# M1501X.net
KiCad netlist of a schematic drawn in EAGLE
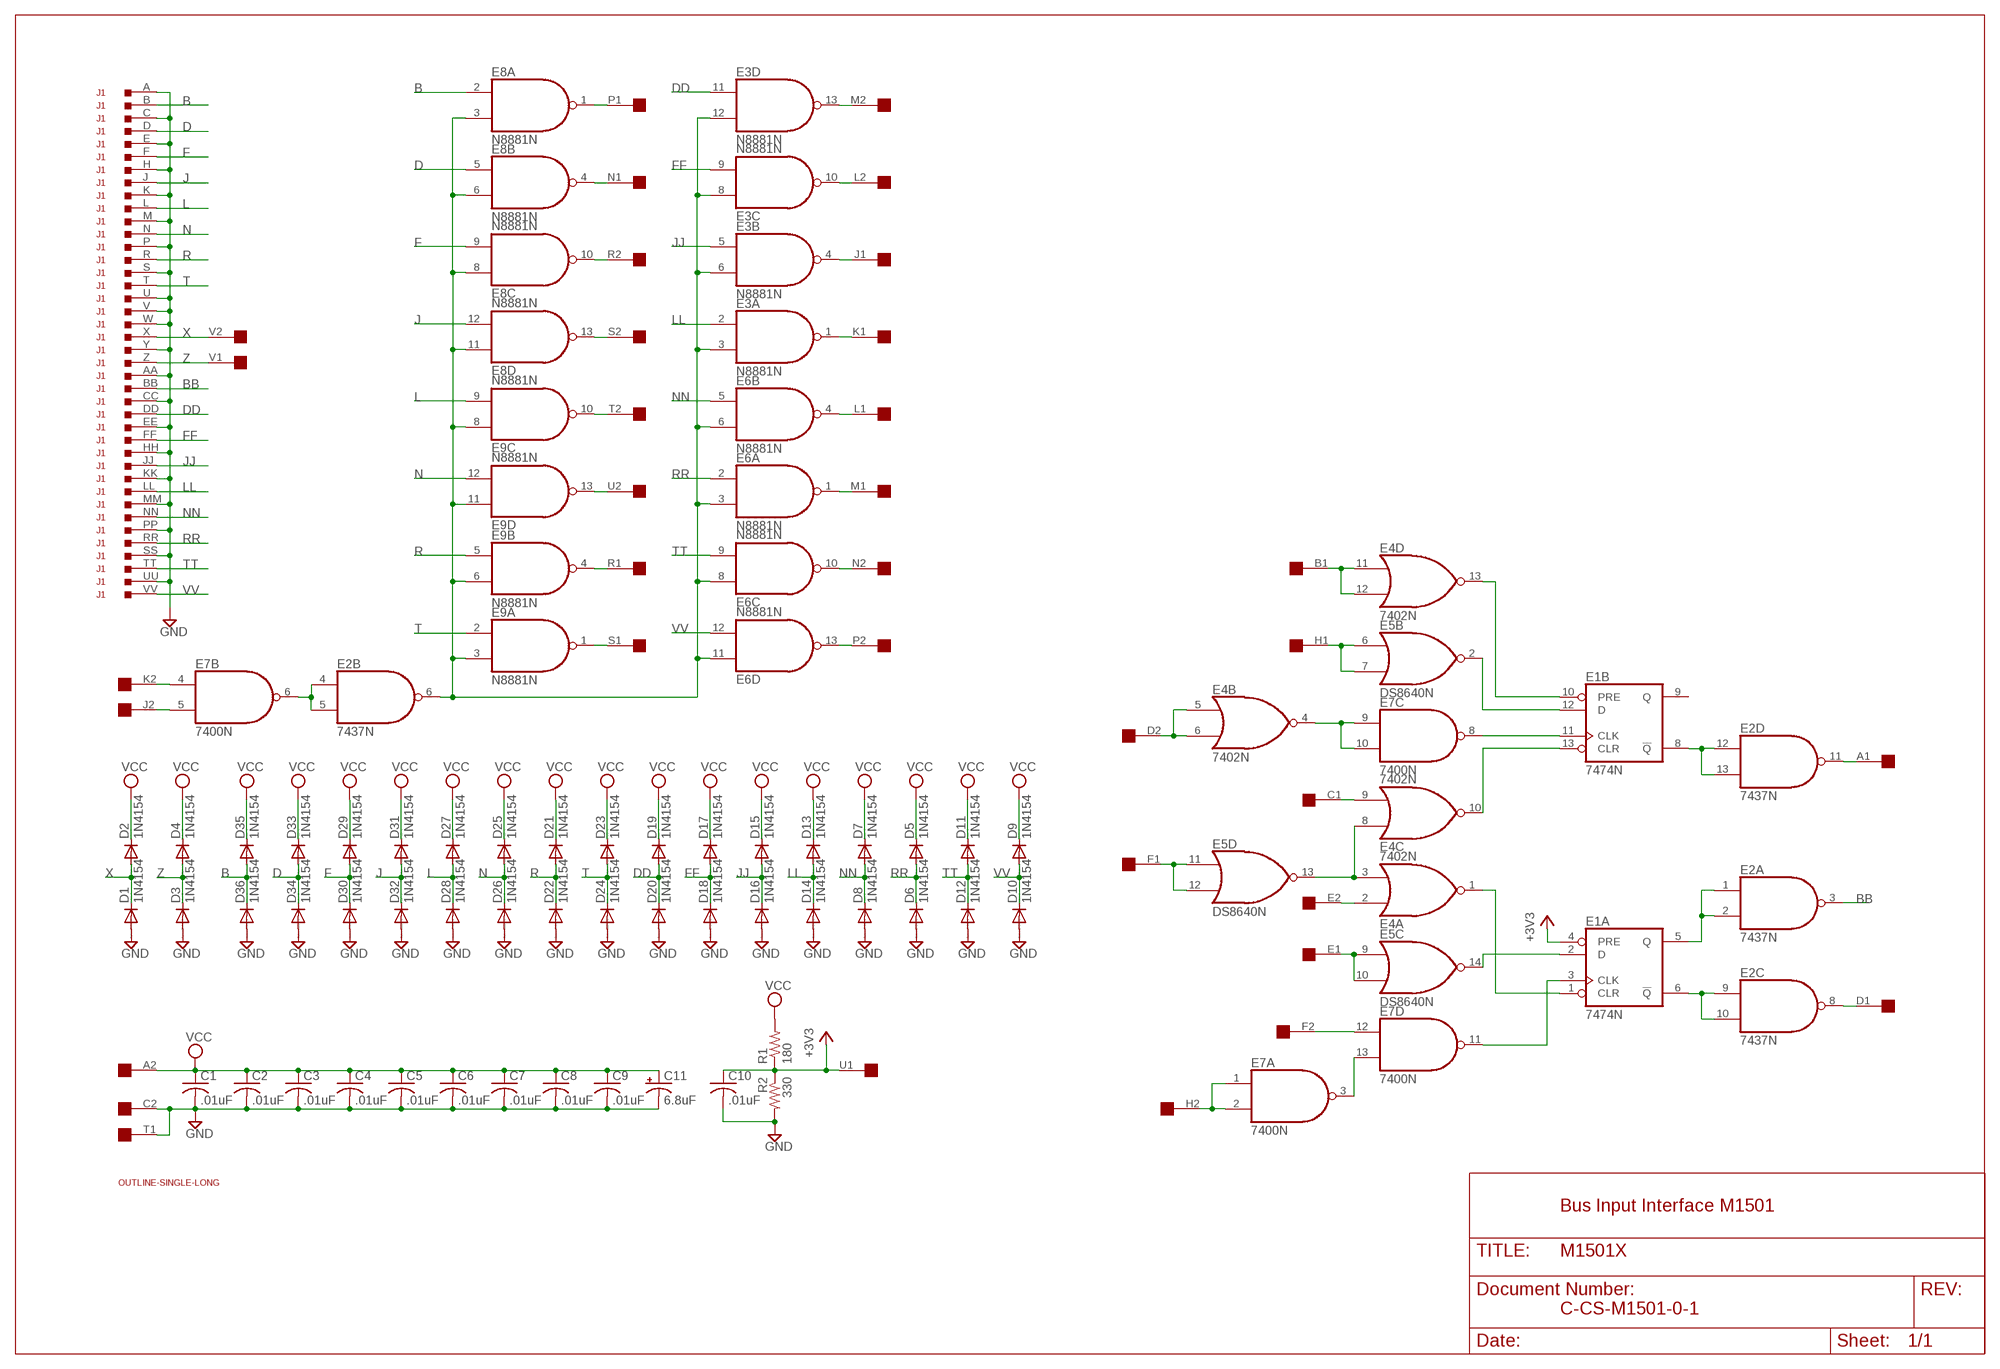
[diagram p0: schematic, sheet 1]

(export (version "E")
  (design (tool "Eeschema 10.0.6"))
  (components
    (comp (ref "C1")
      (value ".01uF")
      (footprint "eagle-import:C050-025X075")
      (libsource (lib "eagle-import") (part "C-US050-025X075"))
    )
    (comp (ref "C2")
      (value ".01uF")
      (footprint "eagle-import:C050-025X075")
      (libsource (lib "eagle-import") (part "C-US050-025X075"))
    )
    (comp (ref "C3")
      (value ".01uF")
      (footprint "eagle-import:C050-025X075")
      (libsource (lib "eagle-import") (part "C-US050-025X075"))
    )
    (comp (ref "C4")
      (value ".01uF")
      (footprint "eagle-import:C050-025X075")
      (libsource (lib "eagle-import") (part "C-US050-025X075"))
    )
    (comp (ref "C5")
      (value ".01uF")
      (footprint "eagle-import:C050-025X075")
      (libsource (lib "eagle-import") (part "C-US050-025X075"))
    )
    (comp (ref "C6")
      (value ".01uF")
      (footprint "eagle-import:C050-025X075")
      (libsource (lib "eagle-import") (part "C-US050-025X075"))
    )
    (comp (ref "C7")
      (value ".01uF")
      (footprint "eagle-import:C050-025X075")
      (libsource (lib "eagle-import") (part "C-US050-025X075"))
    )
    (comp (ref "C8")
      (value ".01uF")
      (footprint "eagle-import:C050-025X075")
      (libsource (lib "eagle-import") (part "C-US050-025X075"))
    )
    (comp (ref "C9")
      (value ".01uF")
      (footprint "eagle-import:C050-025X075")
      (libsource (lib "eagle-import") (part "C-US050-025X075"))
    )
    (comp (ref "C10")
      (value ".01uF")
      (footprint "eagle-import:C050-025X075")
      (libsource (lib "eagle-import") (part "C-US050-025X075"))
    )
    (comp (ref "C11")
      (value "6.8uF")
      (footprint "eagle-import:E12-8")
      (libsource (lib "eagle-import") (part "CPOL-USE20-8AXIAL"))
    )
    (comp (ref "D1")
      (value "1N4154")
      (footprint "eagle-import:DO35-10")
      (libsource (lib "eagle-import") (part "DIODE-DO35-10"))
    )
    (comp (ref "D2")
      (value "1N4154")
      (footprint "eagle-import:DO35-10")
      (libsource (lib "eagle-import") (part "DIODE-DO35-10"))
    )
    (comp (ref "D3")
      (value "1N4154")
      (footprint "eagle-import:DO35-10")
      (libsource (lib "eagle-import") (part "DIODE-DO35-10"))
    )
    (comp (ref "D4")
      (value "1N4154")
      (footprint "eagle-import:DO35-10")
      (libsource (lib "eagle-import") (part "DIODE-DO35-10"))
    )
    (comp (ref "D5")
      (value "1N4154")
      (footprint "eagle-import:DO35-10")
      (libsource (lib "eagle-import") (part "DIODE-DO35-10"))
    )
    (comp (ref "D6")
      (value "1N4154")
      (footprint "eagle-import:DO35-10")
      (libsource (lib "eagle-import") (part "DIODE-DO35-10"))
    )
    (comp (ref "D7")
      (value "1N4154")
      (footprint "eagle-import:DO35-10")
      (libsource (lib "eagle-import") (part "DIODE-DO35-10"))
    )
    (comp (ref "D8")
      (value "1N4154")
      (footprint "eagle-import:DO35-10")
      (libsource (lib "eagle-import") (part "DIODE-DO35-10"))
    )
    (comp (ref "D9")
      (value "1N4154")
      (footprint "eagle-import:DO35-10")
      (libsource (lib "eagle-import") (part "DIODE-DO35-10"))
    )
    (comp (ref "D10")
      (value "1N4154")
      (footprint "eagle-import:DO35-10")
      (libsource (lib "eagle-import") (part "DIODE-DO35-10"))
    )
    (comp (ref "D11")
      (value "1N4154")
      (footprint "eagle-import:DO35-10")
      (libsource (lib "eagle-import") (part "DIODE-DO35-10"))
    )
    (comp (ref "D12")
      (value "1N4154")
      (footprint "eagle-import:DO35-10")
      (libsource (lib "eagle-import") (part "DIODE-DO35-10"))
    )
    (comp (ref "D13")
      (value "1N4154")
      (footprint "eagle-import:DO35-10")
      (libsource (lib "eagle-import") (part "DIODE-DO35-10"))
    )
    (comp (ref "D14")
      (value "1N4154")
      (footprint "eagle-import:DO35-10")
      (libsource (lib "eagle-import") (part "DIODE-DO35-10"))
    )
    (comp (ref "D15")
      (value "1N4154")
      (footprint "eagle-import:DO35-10")
      (libsource (lib "eagle-import") (part "DIODE-DO35-10"))
    )
    (comp (ref "D16")
      (value "1N4154")
      (footprint "eagle-import:DO35-10")
      (libsource (lib "eagle-import") (part "DIODE-DO35-10"))
    )
    (comp (ref "D17")
      (value "1N4154")
      (footprint "eagle-import:DO35-10")
      (libsource (lib "eagle-import") (part "DIODE-DO35-10"))
    )
    (comp (ref "D18")
      (value "1N4154")
      (footprint "eagle-import:DO35-10")
      (libsource (lib "eagle-import") (part "DIODE-DO35-10"))
    )
    (comp (ref "D19")
      (value "1N4154")
      (footprint "eagle-import:DO35-10")
      (libsource (lib "eagle-import") (part "DIODE-DO35-10"))
    )
    (comp (ref "D20")
      (value "1N4154")
      (footprint "eagle-import:DO35-10")
      (libsource (lib "eagle-import") (part "DIODE-DO35-10"))
    )
    (comp (ref "D21")
      (value "1N4154")
      (footprint "eagle-import:DO35-10")
      (libsource (lib "eagle-import") (part "DIODE-DO35-10"))
    )
    (comp (ref "D22")
      (value "1N4154")
      (footprint "eagle-import:DO35-10")
      (libsource (lib "eagle-import") (part "DIODE-DO35-10"))
    )
    (comp (ref "D23")
      (value "1N4154")
      (footprint "eagle-import:DO35-10")
      (libsource (lib "eagle-import") (part "DIODE-DO35-10"))
    )
    (comp (ref "D24")
      (value "1N4154")
      (footprint "eagle-import:DO35-10")
      (libsource (lib "eagle-import") (part "DIODE-DO35-10"))
    )
    (comp (ref "D25")
      (value "1N4154")
      (footprint "eagle-import:DO35-10")
      (libsource (lib "eagle-import") (part "DIODE-DO35-10"))
    )
    (comp (ref "D26")
      (value "1N4154")
      (footprint "eagle-import:DO35-10")
      (libsource (lib "eagle-import") (part "DIODE-DO35-10"))
    )
    (comp (ref "D27")
      (value "1N4154")
      (footprint "eagle-import:DO35-10")
      (libsource (lib "eagle-import") (part "DIODE-DO35-10"))
    )
    (comp (ref "D28")
      (value "1N4154")
      (footprint "eagle-import:DO35-10")
      (libsource (lib "eagle-import") (part "DIODE-DO35-10"))
    )
    (comp (ref "D29")
      (value "1N4154")
      (footprint "eagle-import:DO35-10")
      (libsource (lib "eagle-import") (part "DIODE-DO35-10"))
    )
    (comp (ref "D30")
      (value "1N4154")
      (footprint "eagle-import:DO35-10")
      (libsource (lib "eagle-import") (part "DIODE-DO35-10"))
    )
    (comp (ref "D31")
      (value "1N4154")
      (footprint "eagle-import:DO35-10")
      (libsource (lib "eagle-import") (part "DIODE-DO35-10"))
    )
    (comp (ref "D32")
      (value "1N4154")
      (footprint "eagle-import:DO35-10")
      (libsource (lib "eagle-import") (part "DIODE-DO35-10"))
    )
    (comp (ref "D33")
      (value "1N4154")
      (footprint "eagle-import:DO35-10")
      (libsource (lib "eagle-import") (part "DIODE-DO35-10"))
    )
    (comp (ref "D34")
      (value "1N4154")
      (footprint "eagle-import:DO35-10")
      (libsource (lib "eagle-import") (part "DIODE-DO35-10"))
    )
    (comp (ref "D35")
      (value "1N4154")
      (footprint "eagle-import:DO35-10")
      (libsource (lib "eagle-import") (part "DIODE-DO35-10"))
    )
    (comp (ref "D36")
      (value "1N4154")
      (footprint "eagle-import:DO35-10")
      (libsource (lib "eagle-import") (part "DIODE-DO35-10"))
    )
    (comp (ref "E1")
      (value "7474N")
      (footprint "eagle-import:DIL14")
      (libsource (lib "eagle-import") (part "7474NS"))
    )
    (comp (ref "E2")
      (value "7437N")
      (footprint "eagle-import:DIL14")
      (libsource (lib "eagle-import") (part "7437N"))
    )
    (comp (ref "E3")
      (value "N8881N")
      (footprint "eagle-import:DIL14")
      (libsource (lib "eagle-import") (part "N8881N"))
    )
    (comp (ref "E4")
      (value "7402N")
      (footprint "eagle-import:DIL14")
      (libsource (lib "eagle-import") (part "7402N"))
    )
    (comp (ref "E5")
      (value "DS8640N")
      (footprint "eagle-import:DIL14")
      (libsource (lib "eagle-import") (part "DS8640N"))
    )
    (comp (ref "E6")
      (value "N8881N")
      (footprint "eagle-import:DIL14")
      (libsource (lib "eagle-import") (part "N8881N"))
    )
    (comp (ref "E7")
      (value "7400N")
      (footprint "eagle-import:DIL14")
      (libsource (lib "eagle-import") (part "7400N"))
    )
    (comp (ref "E8")
      (value "N8881N")
      (footprint "eagle-import:DIL14")
      (libsource (lib "eagle-import") (part "N8881N"))
    )
    (comp (ref "E9")
      (value "N8881N")
      (footprint "eagle-import:DIL14")
      (libsource (lib "eagle-import") (part "N8881N"))
    )
    (comp (ref "J1")
      (value "DEC40PINSH")
      (footprint "eagle-import:DEC40PINH")
      (libsource (lib "eagle-import") (part "DEC40PINSH"))
    )
    (comp (ref "R1")
      (value "180")
      (footprint "eagle-import:0207_10")
      (libsource (lib "eagle-import") (part "R-US_0207/10"))
    )
    (comp (ref "R2")
      (value "330")
      (footprint "eagle-import:0207_10")
      (libsource (lib "eagle-import") (part "R-US_0207/10"))
    )
    (comp (ref "U$1")
      (value "OUTLINE-SINGLE-LONG")
      (footprint "eagle-import:SINGLE-LONG")
      (libsource (lib "eagle-import") (part "OUTLINE-SINGLE-LONG"))
    )
    (comp (ref "U$2")
      (value "SINGLE")
      (footprint "eagle-import:EDGE-CON2")
      (libsource (lib "eagle-import") (part "SINGLE"))
    )
  )
  (nets
    (net (code "1") (name "+3V3") (class "Default")
      (node (ref "C10") (pin "1") (pinfunction "1_1") (pintype "passive"))
      (node (ref "E1") (pin "4") (pinfunction "PRE_4") (pintype "input"))
      (node (ref "R1") (pin "1") (pinfunction "1_1") (pintype "passive"))
      (node (ref "R2") (pin "1") (pinfunction "1_1") (pintype "passive"))
      (node (ref "U$2") (pin "U1") (pinfunction "1_U1") (pintype "bidirectional"))
    )
    (net (code "2") (name "/B") (class "Default")
      (node (ref "D35") (pin "A") (pinfunction "A_A") (pintype "passive"))
      (node (ref "D36") (pin "C") (pinfunction "C_C") (pintype "passive"))
      (node (ref "E8") (pin "2") (pinfunction "I0_2") (pintype "input"))
      (node (ref "J1") (pin "B") (pinfunction "P$2_B") (pintype "passive"))
    )
    (net (code "3") (name "/BB") (class "Default")
      (node (ref "E2") (pin "3") (pinfunction "O_3") (pintype "output"))
      (node (ref "J1") (pin "BB") (pinfunction "P$2_BB") (pintype "passive"))
    )
    (net (code "4") (name "/D") (class "Default")
      (node (ref "D33") (pin "A") (pinfunction "A_A") (pintype "passive"))
      (node (ref "D34") (pin "C") (pinfunction "C_C") (pintype "passive"))
      (node (ref "E8") (pin "5") (pinfunction "I0_5") (pintype "input"))
      (node (ref "J1") (pin "D") (pinfunction "P$2_D") (pintype "passive"))
    )
    (net (code "5") (name "/DD") (class "Default")
      (node (ref "D19") (pin "A") (pinfunction "A_A") (pintype "passive"))
      (node (ref "D20") (pin "C") (pinfunction "C_C") (pintype "passive"))
      (node (ref "E3") (pin "11") (pinfunction "I0_11") (pintype "input"))
      (node (ref "J1") (pin "DD") (pinfunction "P$2_DD") (pintype "passive"))
    )
    (net (code "6") (name "/F") (class "Default")
      (node (ref "D29") (pin "A") (pinfunction "A_A") (pintype "passive"))
      (node (ref "D30") (pin "C") (pinfunction "C_C") (pintype "passive"))
      (node (ref "E8") (pin "9") (pinfunction "I1_9") (pintype "input"))
      (node (ref "J1") (pin "F") (pinfunction "P$2_F") (pintype "passive"))
    )
    (net (code "7") (name "/FF") (class "Default")
      (node (ref "D17") (pin "A") (pinfunction "A_A") (pintype "passive"))
      (node (ref "D18") (pin "C") (pinfunction "C_C") (pintype "passive"))
      (node (ref "E3") (pin "9") (pinfunction "I1_9") (pintype "input"))
      (node (ref "J1") (pin "FF") (pinfunction "P$2_FF") (pintype "passive"))
    )
    (net (code "8") (name "/J") (class "Default")
      (node (ref "D31") (pin "A") (pinfunction "A_A") (pintype "passive"))
      (node (ref "D32") (pin "C") (pinfunction "C_C") (pintype "passive"))
      (node (ref "E8") (pin "12") (pinfunction "I1_12") (pintype "input"))
      (node (ref "J1") (pin "J") (pinfunction "P$2_J") (pintype "passive"))
    )
    (net (code "9") (name "/JJ") (class "Default")
      (node (ref "D15") (pin "A") (pinfunction "A_A") (pintype "passive"))
      (node (ref "D16") (pin "C") (pinfunction "C_C") (pintype "passive"))
      (node (ref "E3") (pin "5") (pinfunction "I0_5") (pintype "input"))
      (node (ref "J1") (pin "JJ") (pinfunction "P$2_JJ") (pintype "passive"))
    )
    (net (code "10") (name "/L") (class "Default")
      (node (ref "D27") (pin "A") (pinfunction "A_A") (pintype "passive"))
      (node (ref "D28") (pin "C") (pinfunction "C_C") (pintype "passive"))
      (node (ref "E9") (pin "9") (pinfunction "I1_9") (pintype "input"))
      (node (ref "J1") (pin "L") (pinfunction "P$2_L") (pintype "passive"))
    )
    (net (code "11") (name "/LL") (class "Default")
      (node (ref "D13") (pin "A") (pinfunction "A_A") (pintype "passive"))
      (node (ref "D14") (pin "C") (pinfunction "C_C") (pintype "passive"))
      (node (ref "E3") (pin "2") (pinfunction "I0_2") (pintype "input"))
      (node (ref "J1") (pin "LL") (pinfunction "P$2_LL") (pintype "passive"))
    )
    (net (code "12") (name "/N") (class "Default")
      (node (ref "D25") (pin "A") (pinfunction "A_A") (pintype "passive"))
      (node (ref "D26") (pin "C") (pinfunction "C_C") (pintype "passive"))
      (node (ref "E9") (pin "12") (pinfunction "I1_12") (pintype "input"))
      (node (ref "J1") (pin "N") (pinfunction "P$2_N") (pintype "passive"))
    )
    (net (code "13") (name "/NN") (class "Default")
      (node (ref "D7") (pin "A") (pinfunction "A_A") (pintype "passive"))
      (node (ref "D8") (pin "C") (pinfunction "C_C") (pintype "passive"))
      (node (ref "E6") (pin "5") (pinfunction "I0_5") (pintype "input"))
      (node (ref "J1") (pin "NN") (pinfunction "P$2_NN") (pintype "passive"))
    )
    (net (code "14") (name "/R") (class "Default")
      (node (ref "D21") (pin "A") (pinfunction "A_A") (pintype "passive"))
      (node (ref "D22") (pin "C") (pinfunction "C_C") (pintype "passive"))
      (node (ref "E9") (pin "5") (pinfunction "I0_5") (pintype "input"))
      (node (ref "J1") (pin "R") (pinfunction "P$2_R") (pintype "passive"))
    )
    (net (code "15") (name "/RR") (class "Default")
      (node (ref "D5") (pin "A") (pinfunction "A_A") (pintype "passive"))
      (node (ref "D6") (pin "C") (pinfunction "C_C") (pintype "passive"))
      (node (ref "E6") (pin "2") (pinfunction "I0_2") (pintype "input"))
      (node (ref "J1") (pin "RR") (pinfunction "P$2_RR") (pintype "passive"))
    )
    (net (code "16") (name "/T") (class "Default")
      (node (ref "D23") (pin "A") (pinfunction "A_A") (pintype "passive"))
      (node (ref "D24") (pin "C") (pinfunction "C_C") (pintype "passive"))
      (node (ref "E9") (pin "2") (pinfunction "I0_2") (pintype "input"))
      (node (ref "J1") (pin "T") (pinfunction "P$2_T") (pintype "passive"))
    )
    (net (code "17") (name "/TT") (class "Default")
      (node (ref "D11") (pin "A") (pinfunction "A_A") (pintype "passive"))
      (node (ref "D12") (pin "C") (pinfunction "C_C") (pintype "passive"))
      (node (ref "E6") (pin "9") (pinfunction "I1_9") (pintype "input"))
      (node (ref "J1") (pin "TT") (pinfunction "P$2_TT") (pintype "passive"))
    )
    (net (code "18") (name "/VV") (class "Default")
      (node (ref "D10") (pin "C") (pinfunction "C_C") (pintype "passive"))
      (node (ref "D9") (pin "A") (pinfunction "A_A") (pintype "passive"))
      (node (ref "E6") (pin "12") (pinfunction "I1_12") (pintype "input"))
      (node (ref "J1") (pin "VV") (pinfunction "P$2_VV") (pintype "passive"))
    )
    (net (code "19") (name "/X") (class "Default")
      (node (ref "D1") (pin "C") (pinfunction "C_C") (pintype "passive"))
      (node (ref "D2") (pin "A") (pinfunction "A_A") (pintype "passive"))
      (node (ref "J1") (pin "X") (pinfunction "P$2_X") (pintype "passive"))
      (node (ref "U$2") (pin "V2") (pinfunction "1_V2") (pintype "bidirectional"))
    )
    (net (code "20") (name "/Z") (class "Default")
      (node (ref "D3") (pin "C") (pinfunction "C_C") (pintype "passive"))
      (node (ref "D4") (pin "A") (pinfunction "A_A") (pintype "passive"))
      (node (ref "J1") (pin "Z") (pinfunction "P$2_Z") (pintype "passive"))
      (node (ref "U$2") (pin "V1") (pinfunction "1_V1") (pintype "bidirectional"))
    )
    (net (code "21") (name "GND") (class "Default")
      (node (ref "C1") (pin "2") (pinfunction "2_2") (pintype "passive"))
      (node (ref "C10") (pin "2") (pinfunction "2_2") (pintype "passive"))
      (node (ref "C11") (pin "-") (pinfunction "-_-") (pintype "passive"))
      (node (ref "C2") (pin "2") (pinfunction "2_2") (pintype "passive"))
      (node (ref "C3") (pin "2") (pinfunction "2_2") (pintype "passive"))
      (node (ref "C4") (pin "2") (pinfunction "2_2") (pintype "passive"))
      (node (ref "C5") (pin "2") (pinfunction "2_2") (pintype "passive"))
      (node (ref "C6") (pin "2") (pinfunction "2_2") (pintype "passive"))
      (node (ref "C7") (pin "2") (pinfunction "2_2") (pintype "passive"))
      (node (ref "C8") (pin "2") (pinfunction "2_2") (pintype "passive"))
      (node (ref "C9") (pin "2") (pinfunction "2_2") (pintype "passive"))
      (node (ref "D1") (pin "A") (pinfunction "A_A") (pintype "passive"))
      (node (ref "D10") (pin "A") (pinfunction "A_A") (pintype "passive"))
      (node (ref "D12") (pin "A") (pinfunction "A_A") (pintype "passive"))
      (node (ref "D14") (pin "A") (pinfunction "A_A") (pintype "passive"))
      (node (ref "D16") (pin "A") (pinfunction "A_A") (pintype "passive"))
      (node (ref "D18") (pin "A") (pinfunction "A_A") (pintype "passive"))
      (node (ref "D20") (pin "A") (pinfunction "A_A") (pintype "passive"))
      (node (ref "D22") (pin "A") (pinfunction "A_A") (pintype "passive"))
      (node (ref "D24") (pin "A") (pinfunction "A_A") (pintype "passive"))
      (node (ref "D26") (pin "A") (pinfunction "A_A") (pintype "passive"))
      (node (ref "D28") (pin "A") (pinfunction "A_A") (pintype "passive"))
      (node (ref "D3") (pin "A") (pinfunction "A_A") (pintype "passive"))
      (node (ref "D30") (pin "A") (pinfunction "A_A") (pintype "passive"))
      (node (ref "D32") (pin "A") (pinfunction "A_A") (pintype "passive"))
      (node (ref "D34") (pin "A") (pinfunction "A_A") (pintype "passive"))
      (node (ref "D36") (pin "A") (pinfunction "A_A") (pintype "passive"))
      (node (ref "D6") (pin "A") (pinfunction "A_A") (pintype "passive"))
      (node (ref "D8") (pin "A") (pinfunction "A_A") (pintype "passive"))
      (node (ref "J1") (pin "A") (pinfunction "P$2_A") (pintype "passive"))
      (node (ref "J1") (pin "AA") (pinfunction "P$2_AA") (pintype "passive"))
      (node (ref "J1") (pin "C") (pinfunction "P$2_C") (pintype "passive"))
      (node (ref "J1") (pin "CC") (pinfunction "P$2_CC") (pintype "passive"))
      (node (ref "J1") (pin "E") (pinfunction "P$2_E") (pintype "passive"))
      (node (ref "J1") (pin "EE") (pinfunction "P$2_EE") (pintype "passive"))
      (node (ref "J1") (pin "H") (pinfunction "P$2_H") (pintype "passive"))
      (node (ref "J1") (pin "HH") (pinfunction "P$2_HH") (pintype "passive"))
      (node (ref "J1") (pin "K") (pinfunction "P$2_K") (pintype "passive"))
      (node (ref "J1") (pin "KK") (pinfunction "P$2_KK") (pintype "passive"))
      (node (ref "J1") (pin "M") (pinfunction "P$2_M") (pintype "passive"))
      (node (ref "J1") (pin "MM") (pinfunction "P$2_MM") (pintype "passive"))
      (node (ref "J1") (pin "P") (pinfunction "P$2_P") (pintype "passive"))
      (node (ref "J1") (pin "PP") (pinfunction "P$2_PP") (pintype "passive"))
      (node (ref "J1") (pin "S") (pinfunction "P$2_S") (pintype "passive"))
      (node (ref "J1") (pin "SS") (pinfunction "P$2_SS") (pintype "passive"))
      (node (ref "J1") (pin "U") (pinfunction "P$2_U") (pintype "passive"))
      (node (ref "J1") (pin "UU") (pinfunction "P$2_UU") (pintype "passive"))
      (node (ref "J1") (pin "V") (pinfunction "P$2_V") (pintype "passive"))
      (node (ref "J1") (pin "W") (pinfunction "P$2_W") (pintype "passive"))
      (node (ref "J1") (pin "Y") (pinfunction "P$2_Y") (pintype "passive"))
      (node (ref "R2") (pin "2") (pinfunction "2_2") (pintype "passive"))
      (node (ref "U$2") (pin "C2") (pinfunction "1_C2") (pintype "bidirectional"))
      (node (ref "U$2") (pin "T1") (pinfunction "1_T1") (pintype "bidirectional"))
    )
    (net (code "22") (name "Net-(E1A-CLK)") (class "Default")
      (node (ref "E1") (pin "3") (pinfunction "CLK_3") (pintype "input"))
      (node (ref "E7") (pin "11") (pinfunction "O_11") (pintype "output"))
    )
    (net (code "23") (name "Net-(E1A-CLR)") (class "Default")
      (node (ref "E1") (pin "1") (pinfunction "CLR_1") (pintype "input"))
      (node (ref "E4") (pin "1") (pinfunction "O_1") (pintype "output"))
    )
    (net (code "24") (name "Net-(E1A-D)") (class "Default")
      (node (ref "E1") (pin "2") (pinfunction "D_2") (pintype "input"))
      (node (ref "E5") (pin "14") (pinfunction "O_14") (pintype "output"))
    )
    (net (code "25") (name "Net-(E1A-Q)") (class "Default")
      (node (ref "E1") (pin "5") (pinfunction "Q_5") (pintype "output"))
      (node (ref "E2") (pin "1") (pinfunction "I0_1") (pintype "input"))
      (node (ref "E2") (pin "2") (pinfunction "I1_2") (pintype "input"))
    )
    (net (code "26") (name "Net-(E1A-~{Q})") (class "Default")
      (node (ref "E1") (pin "6") (pinfunction "~{Q}_6") (pintype "output"))
      (node (ref "E2") (pin "10") (pinfunction "I1_10") (pintype "input"))
      (node (ref "E2") (pin "9") (pinfunction "I0_9") (pintype "input"))
    )
    (net (code "27") (name "Net-(E1B-CLK)") (class "Default")
      (node (ref "E1") (pin "11") (pinfunction "CLK_11") (pintype "input"))
      (node (ref "E7") (pin "8") (pinfunction "O_8") (pintype "output"))
    )
    (net (code "28") (name "Net-(E1B-CLR)") (class "Default")
      (node (ref "E1") (pin "13") (pinfunction "CLR_13") (pintype "input"))
      (node (ref "E4") (pin "10") (pinfunction "O_10") (pintype "output"))
    )
    (net (code "29") (name "Net-(E1B-D)") (class "Default")
      (node (ref "E1") (pin "12") (pinfunction "D_12") (pintype "input"))
      (node (ref "E5") (pin "2") (pinfunction "O_2") (pintype "output"))
    )
    (net (code "30") (name "Net-(E1B-PRE)") (class "Default")
      (node (ref "E1") (pin "10") (pinfunction "PRE_10") (pintype "input"))
      (node (ref "E4") (pin "13") (pinfunction "O_13") (pintype "output"))
    )
    (net (code "31") (name "Net-(E1B-~{Q})") (class "Default")
      (node (ref "E1") (pin "8") (pinfunction "~{Q}_8") (pintype "output"))
      (node (ref "E2") (pin "12") (pinfunction "I0_12") (pintype "input"))
      (node (ref "E2") (pin "13") (pinfunction "I1_13") (pintype "input"))
    )
    (net (code "32") (name "Net-(E2B-I0)") (class "Default")
      (node (ref "E2") (pin "4") (pinfunction "I0_4") (pintype "input"))
      (node (ref "E2") (pin "5") (pinfunction "I1_5") (pintype "input"))
      (node (ref "E7") (pin "6") (pinfunction "O_6") (pintype "output"))
    )
    (net (code "33") (name "Net-(E2B-O)") (class "Default")
      (node (ref "E2") (pin "6") (pinfunction "O_6") (pintype "output"))
      (node (ref "E3") (pin "12") (pinfunction "I1_12") (pintype "input"))
      (node (ref "E3") (pin "3") (pinfunction "I1_3") (pintype "input"))
      (node (ref "E3") (pin "6") (pinfunction "I1_6") (pintype "input"))
      (node (ref "E3") (pin "8") (pinfunction "I0_8") (pintype "input"))
      (node (ref "E6") (pin "11") (pinfunction "I0_11") (pintype "input"))
      (node (ref "E6") (pin "3") (pinfunction "I1_3") (pintype "input"))
      (node (ref "E6") (pin "6") (pinfunction "I1_6") (pintype "input"))
      (node (ref "E6") (pin "8") (pinfunction "I0_8") (pintype "input"))
      (node (ref "E8") (pin "11") (pinfunction "I0_11") (pintype "input"))
      (node (ref "E8") (pin "3") (pinfunction "I1_3") (pintype "input"))
      (node (ref "E8") (pin "6") (pinfunction "I1_6") (pintype "input"))
      (node (ref "E8") (pin "8") (pinfunction "I0_8") (pintype "input"))
      (node (ref "E9") (pin "11") (pinfunction "I0_11") (pintype "input"))
      (node (ref "E9") (pin "3") (pinfunction "I1_3") (pintype "input"))
      (node (ref "E9") (pin "6") (pinfunction "I1_6") (pintype "input"))
      (node (ref "E9") (pin "8") (pinfunction "I0_8") (pintype "input"))
    )
    (net (code "34") (name "Net-(E2C-O)") (class "Default")
      (node (ref "E2") (pin "8") (pinfunction "O_8") (pintype "output"))
      (node (ref "U$2") (pin "D1") (pinfunction "1_D1") (pintype "bidirectional"))
    )
    (net (code "35") (name "Net-(E2D-O)") (class "Default")
      (node (ref "E2") (pin "11") (pinfunction "O_11") (pintype "output"))
      (node (ref "U$2") (pin "A1") (pinfunction "1_A1") (pintype "bidirectional"))
    )
    (net (code "36") (name "Net-(E3A-O)") (class "Default")
      (node (ref "E3") (pin "1") (pinfunction "O_1") (pintype "open_collector"))
      (node (ref "U$2") (pin "K1") (pinfunction "1_K1") (pintype "bidirectional"))
    )
    (net (code "37") (name "Net-(E3B-O)") (class "Default")
      (node (ref "E3") (pin "4") (pinfunction "O_4") (pintype "open_collector"))
      (node (ref "U$2") (pin "J1") (pinfunction "1_J1") (pintype "bidirectional"))
    )
    (net (code "38") (name "Net-(E3C-O)") (class "Default")
      (node (ref "E3") (pin "10") (pinfunction "O_10") (pintype "open_collector"))
      (node (ref "U$2") (pin "L2") (pinfunction "1_L2") (pintype "bidirectional"))
    )
    (net (code "39") (name "Net-(E3D-O)") (class "Default")
      (node (ref "E3") (pin "13") (pinfunction "O_13") (pintype "open_collector"))
      (node (ref "U$2") (pin "M2") (pinfunction "1_M2") (pintype "bidirectional"))
    )
    (net (code "40") (name "Net-(E4A-I0)") (class "Default")
      (node (ref "E4") (pin "2") (pinfunction "I0_2") (pintype "input"))
      (node (ref "U$2") (pin "E2") (pinfunction "1_E2") (pintype "bidirectional"))
    )
    (net (code "41") (name "Net-(E4A-I1)") (class "Default")
      (node (ref "E4") (pin "3") (pinfunction "I1_3") (pintype "input"))
      (node (ref "E4") (pin "8") (pinfunction "I0_8") (pintype "input"))
      (node (ref "E5") (pin "13") (pinfunction "O_13") (pintype "output"))
    )
    (net (code "42") (name "Net-(E4B-I0)") (class "Default")
      (node (ref "E4") (pin "5") (pinfunction "I0_5") (pintype "input"))
      (node (ref "E4") (pin "6") (pinfunction "I1_6") (pintype "input"))
      (node (ref "U$2") (pin "D2") (pinfunction "1_D2") (pintype "bidirectional"))
    )
    (net (code "43") (name "Net-(E4B-O)") (class "Default")
      (node (ref "E4") (pin "4") (pinfunction "O_4") (pintype "output"))
      (node (ref "E7") (pin "10") (pinfunction "I1_10") (pintype "input"))
      (node (ref "E7") (pin "9") (pinfunction "I0_9") (pintype "input"))
    )
    (net (code "44") (name "Net-(E4C-I1)") (class "Default")
      (node (ref "E4") (pin "9") (pinfunction "I1_9") (pintype "input"))
      (node (ref "U$2") (pin "C1") (pinfunction "1_C1") (pintype "bidirectional"))
    )
    (net (code "45") (name "Net-(E4D-I0)") (class "Default")
      (node (ref "E4") (pin "11") (pinfunction "I0_11") (pintype "input"))
      (node (ref "E4") (pin "12") (pinfunction "I1_12") (pintype "input"))
      (node (ref "U$2") (pin "B1") (pinfunction "1_B1") (pintype "bidirectional"))
    )
    (net (code "46") (name "Net-(E5B-I0)") (class "Default")
      (node (ref "E5") (pin "6") (pinfunction "I0_6") (pintype "input"))
      (node (ref "E5") (pin "7") (pinfunction "I1_7") (pintype "input"))
      (node (ref "U$2") (pin "H1") (pinfunction "1_H1") (pintype "bidirectional"))
    )
    (net (code "47") (name "Net-(E5C-I0)") (class "Default")
      (node (ref "E5") (pin "10") (pinfunction "I1_10") (pintype "input"))
      (node (ref "E5") (pin "9") (pinfunction "I0_9") (pintype "input"))
      (node (ref "U$2") (pin "E1") (pinfunction "1_E1") (pintype "bidirectional"))
    )
    (net (code "48") (name "Net-(E5D-I0)") (class "Default")
      (node (ref "E5") (pin "11") (pinfunction "I0_11") (pintype "input"))
      (node (ref "E5") (pin "12") (pinfunction "I1_12") (pintype "input"))
      (node (ref "U$2") (pin "F1") (pinfunction "1_F1") (pintype "bidirectional"))
    )
    (net (code "49") (name "Net-(E6A-O)") (class "Default")
      (node (ref "E6") (pin "1") (pinfunction "O_1") (pintype "open_collector"))
      (node (ref "U$2") (pin "M1") (pinfunction "1_M1") (pintype "bidirectional"))
    )
    (net (code "50") (name "Net-(E6B-O)") (class "Default")
      (node (ref "E6") (pin "4") (pinfunction "O_4") (pintype "open_collector"))
      (node (ref "U$2") (pin "L1") (pinfunction "1_L1") (pintype "bidirectional"))
    )
    (net (code "51") (name "Net-(E6C-O)") (class "Default")
      (node (ref "E6") (pin "10") (pinfunction "O_10") (pintype "open_collector"))
      (node (ref "U$2") (pin "N2") (pinfunction "1_N2") (pintype "bidirectional"))
    )
    (net (code "52") (name "Net-(E6D-O)") (class "Default")
      (node (ref "E6") (pin "13") (pinfunction "O_13") (pintype "open_collector"))
      (node (ref "U$2") (pin "P2") (pinfunction "1_P2") (pintype "bidirectional"))
    )
    (net (code "53") (name "Net-(E7A-I0)") (class "Default")
      (node (ref "E7") (pin "1") (pinfunction "I0_1") (pintype "input"))
      (node (ref "E7") (pin "2") (pinfunction "I1_2") (pintype "input"))
      (node (ref "U$2") (pin "H2") (pinfunction "1_H2") (pintype "bidirectional"))
    )
    (net (code "54") (name "Net-(E7A-O)") (class "Default")
      (node (ref "E7") (pin "13") (pinfunction "I1_13") (pintype "input"))
      (node (ref "E7") (pin "3") (pinfunction "O_3") (pintype "output"))
    )
    (net (code "55") (name "Net-(E7B-I0)") (class "Default")
      (node (ref "E7") (pin "4") (pinfunction "I0_4") (pintype "input"))
      (node (ref "U$2") (pin "K2") (pinfunction "1_K2") (pintype "bidirectional"))
    )
    (net (code "56") (name "Net-(E7B-I1)") (class "Default")
      (node (ref "E7") (pin "5") (pinfunction "I1_5") (pintype "input"))
      (node (ref "U$2") (pin "J2") (pinfunction "1_J2") (pintype "bidirectional"))
    )
    (net (code "57") (name "Net-(E7D-I0)") (class "Default")
      (node (ref "E7") (pin "12") (pinfunction "I0_12") (pintype "input"))
      (node (ref "U$2") (pin "F2") (pinfunction "1_F2") (pintype "bidirectional"))
    )
    (net (code "58") (name "Net-(E8A-O)") (class "Default")
      (node (ref "E8") (pin "1") (pinfunction "O_1") (pintype "open_collector"))
      (node (ref "U$2") (pin "P1") (pinfunction "1_P1") (pintype "bidirectional"))
    )
    (net (code "59") (name "Net-(E8B-O)") (class "Default")
      (node (ref "E8") (pin "4") (pinfunction "O_4") (pintype "open_collector"))
      (node (ref "U$2") (pin "N1") (pinfunction "1_N1") (pintype "bidirectional"))
    )
    (net (code "60") (name "Net-(E8C-O)") (class "Default")
      (node (ref "E8") (pin "10") (pinfunction "O_10") (pintype "open_collector"))
      (node (ref "U$2") (pin "R2") (pinfunction "1_R2") (pintype "bidirectional"))
    )
    (net (code "61") (name "Net-(E8D-O)") (class "Default")
      (node (ref "E8") (pin "13") (pinfunction "O_13") (pintype "open_collector"))
      (node (ref "U$2") (pin "S2") (pinfunction "1_S2") (pintype "bidirectional"))
    )
    (net (code "62") (name "Net-(E9A-O)") (class "Default")
      (node (ref "E9") (pin "1") (pinfunction "O_1") (pintype "open_collector"))
      (node (ref "U$2") (pin "S1") (pinfunction "1_S1") (pintype "bidirectional"))
    )
    (net (code "63") (name "Net-(E9B-O)") (class "Default")
      (node (ref "E9") (pin "4") (pinfunction "O_4") (pintype "open_collector"))
      (node (ref "U$2") (pin "R1") (pinfunction "1_R1") (pintype "bidirectional"))
    )
    (net (code "64") (name "Net-(E9C-O)") (class "Default")
      (node (ref "E9") (pin "10") (pinfunction "O_10") (pintype "open_collector"))
      (node (ref "U$2") (pin "T2") (pinfunction "1_T2") (pintype "bidirectional"))
    )
    (net (code "65") (name "Net-(E9D-O)") (class "Default")
      (node (ref "E9") (pin "13") (pinfunction "O_13") (pintype "open_collector"))
      (node (ref "U$2") (pin "U2") (pinfunction "1_U2") (pintype "bidirectional"))
    )
    (net (code "66") (name "VCC") (class "Default")
      (node (ref "C1") (pin "1") (pinfunction "1_1") (pintype "passive"))
      (node (ref "C11") (pin "+") (pinfunction "+_+") (pintype "passive"))
      (node (ref "C2") (pin "1") (pinfunction "1_1") (pintype "passive"))
      (node (ref "C3") (pin "1") (pinfunction "1_1") (pintype "passive"))
      (node (ref "C4") (pin "1") (pinfunction "1_1") (pintype "passive"))
      (node (ref "C5") (pin "1") (pinfunction "1_1") (pintype "passive"))
      (node (ref "C6") (pin "1") (pinfunction "1_1") (pintype "passive"))
      (node (ref "C7") (pin "1") (pinfunction "1_1") (pintype "passive"))
      (node (ref "C8") (pin "1") (pinfunction "1_1") (pintype "passive"))
      (node (ref "C9") (pin "1") (pinfunction "1_1") (pintype "passive"))
      (node (ref "D11") (pin "C") (pinfunction "C_C") (pintype "passive"))
      (node (ref "D13") (pin "C") (pinfunction "C_C") (pintype "passive"))
      (node (ref "D15") (pin "C") (pinfunction "C_C") (pintype "passive"))
      (node (ref "D17") (pin "C") (pinfunction "C_C") (pintype "passive"))
      (node (ref "D19") (pin "C") (pinfunction "C_C") (pintype "passive"))
      (node (ref "D2") (pin "C") (pinfunction "C_C") (pintype "passive"))
      (node (ref "D21") (pin "C") (pinfunction "C_C") (pintype "passive"))
      (node (ref "D23") (pin "C") (pinfunction "C_C") (pintype "passive"))
      (node (ref "D25") (pin "C") (pinfunction "C_C") (pintype "passive"))
      (node (ref "D27") (pin "C") (pinfunction "C_C") (pintype "passive"))
      (node (ref "D29") (pin "C") (pinfunction "C_C") (pintype "passive"))
      (node (ref "D31") (pin "C") (pinfunction "C_C") (pintype "passive"))
      (node (ref "D33") (pin "C") (pinfunction "C_C") (pintype "passive"))
      (node (ref "D35") (pin "C") (pinfunction "C_C") (pintype "passive"))
      (node (ref "D4") (pin "C") (pinfunction "C_C") (pintype "passive"))
      (node (ref "D5") (pin "C") (pinfunction "C_C") (pintype "passive"))
      (node (ref "D7") (pin "C") (pinfunction "C_C") (pintype "passive"))
      (node (ref "D9") (pin "C") (pinfunction "C_C") (pintype "passive"))
      (node (ref "R1") (pin "2") (pinfunction "2_2") (pintype "passive"))
      (node (ref "U$2") (pin "A2") (pinfunction "1_A2") (pintype "bidirectional"))
    )
    (net (code "67") (name "unconnected-(E1B-Q-Pad9)") (class "Default")
      (node (ref "E1") (pin "9") (pinfunction "Q_9") (pintype "output"))
    )
  )
)
